# Low_MOS.net
KiCad netlist of a schematic drawn in Altium Designer
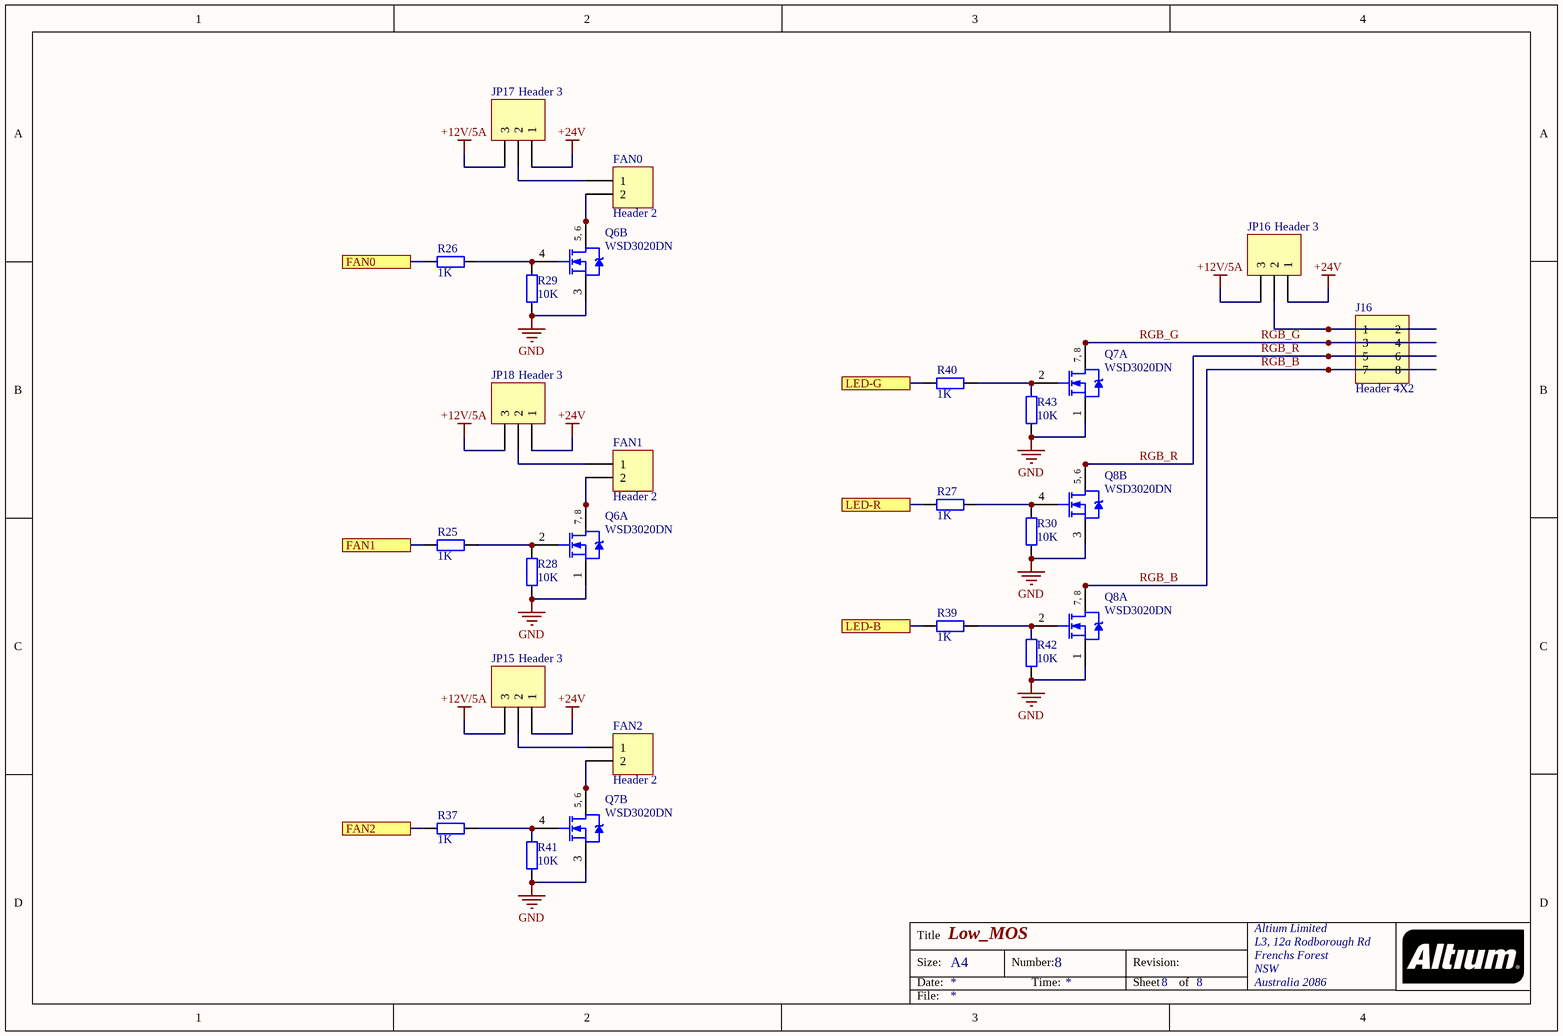
[diagram p0: Low_MOS.SchDoc]

(export (version "E")
  (design (tool "Eeschema 10.0.6"))
  (components
    (comp (ref "FAN0")
      (value "Header 2")
      (footprint "1X2 MTE STRAIGHT HEADER 2.54MM")
      (description "Header, 2-Pin")
      (fields (field (name "PUBLISHER") "Altium Limited"))
      (libsource (lib "Miscellaneous Connectors") (part "Header 2"))
    )
    (comp (ref "FAN1")
      (value "Header 2")
      (footprint "1X2 MTE STRAIGHT HEADER 2.54MM")
      (description "Header, 2-Pin")
      (fields (field (name "PUBLISHER") "Altium Limited"))
      (libsource (lib "Miscellaneous Connectors") (part "Header 2"))
    )
    (comp (ref "FAN2")
      (value "Header 2")
      (footprint "1X2 MTE STRAIGHT HEADER 2.54MM")
      (description "Header, 2-Pin")
      (fields (field (name "PUBLISHER") "Altium Limited"))
      (libsource (lib "Miscellaneous Connectors") (part "Header 2"))
    )
    (comp (ref "J16")
      (value "Header 4X2")
      (footprint "Header 2X4")
      (description "Header, 4-Pin, Dual row")
      (fields (field (name "PUBLISHER") "Altium Limited"))
      (libsource (lib "Miscellaneous Connectors") (part "Header 4X2"))
    )
    (comp (ref "JP15")
      (value "Header 3")
      (footprint "Header 1X3")
      (description "Header, 3-Pin")
      (fields (field (name "PUBLISHER") "Altium Limited"))
      (libsource (lib "Miscellaneous Connectors") (part "Header 3"))
    )
    (comp (ref "JP16")
      (value "Header 3")
      (footprint "Header 1X3")
      (description "Header, 3-Pin")
      (fields (field (name "PUBLISHER") "Altium Limited"))
      (libsource (lib "Miscellaneous Connectors") (part "Header 3"))
    )
    (comp (ref "JP17")
      (value "Header 3")
      (footprint "Header 1X3")
      (description "Header, 3-Pin")
      (fields (field (name "PUBLISHER") "Altium Limited"))
      (libsource (lib "Miscellaneous Connectors") (part "Header 3"))
    )
    (comp (ref "JP18")
      (value "Header 3")
      (footprint "Header 1X3")
      (description "Header, 3-Pin")
      (fields (field (name "PUBLISHER") "Altium Limited"))
      (libsource (lib "Miscellaneous Connectors") (part "Header 3"))
    )
    (comp (ref "Q6")
      (value "WSD3020DN")
      (footprint "DFN3X3-8L-Dual")
      (description "HEXFET Power MOSFET")
      (fields (field (name "PUBLISHER") "Altium Limited"))
      (libsource (lib "IR Discrete MOSFET - Power") (part "IRF7103"))
    )
    (comp (ref "Q7")
      (value "WSD3020DN")
      (footprint "DFN3X3-8L-Dual")
      (description "HEXFET Power MOSFET")
      (fields (field (name "PUBLISHER") "Altium Limited"))
      (libsource (lib "IR Discrete MOSFET - Power") (part "IRF7103"))
    )
    (comp (ref "Q8")
      (value "WSD3020DN")
      (footprint "DFN3X3-8L-Dual")
      (description "HEXFET Power MOSFET")
      (fields (field (name "PUBLISHER") "Altium Limited"))
      (libsource (lib "IR Discrete MOSFET - Power") (part "IRF7103"))
    )
    (comp (ref "R25") (value "1K") (footprint "RES0402") (libsource (lib "接插件库") (part "Resistor")))
    (comp (ref "R26") (value "1K") (footprint "RES0402") (libsource (lib "接插件库") (part "Resistor")))
    (comp (ref "R27") (value "1K") (footprint "RES0402") (libsource (lib "接插件库") (part "Resistor")))
    (comp (ref "R28") (value "10K") (footprint "RES0402") (libsource (lib "") (part "Resistor_1")))
    (comp (ref "R29") (value "10K") (footprint "RES0402") (libsource (lib "") (part "Resistor_1")))
    (comp (ref "R30") (value "10K") (footprint "RES0402") (libsource (lib "") (part "Resistor_1")))
    (comp (ref "R37") (value "1K") (footprint "RES0402") (libsource (lib "接插件库") (part "Resistor")))
    (comp (ref "R39") (value "1K") (footprint "RES0402") (libsource (lib "接插件库") (part "Resistor")))
    (comp (ref "R40") (value "1K") (footprint "RES0402") (libsource (lib "接插件库") (part "Resistor")))
    (comp (ref "R41") (value "10K") (footprint "RES0402") (libsource (lib "") (part "Resistor_1")))
    (comp (ref "R42") (value "10K") (footprint "RES0402") (libsource (lib "") (part "Resistor_1")))
    (comp (ref "R43") (value "10K") (footprint "RES0402") (libsource (lib "") (part "Resistor_1")))
  )
  (nets
    (net (code "1") (name "+12V{slash}5A") (class "Default")
      (node (ref "JP15") (pin "3") (pinfunction "3_3") (pintype "passive"))
      (node (ref "JP16") (pin "3") (pinfunction "3_3") (pintype "passive"))
      (node (ref "JP17") (pin "3") (pinfunction "3_3") (pintype "passive"))
      (node (ref "JP18") (pin "3") (pinfunction "3_3") (pintype "passive"))
    )
    (net (code "2") (name "+24V") (class "Default")
      (node (ref "JP15") (pin "1") (pinfunction "1_1") (pintype "passive"))
      (node (ref "JP16") (pin "1") (pinfunction "1_1") (pintype "passive"))
      (node (ref "JP17") (pin "1") (pinfunction "1_1") (pintype "passive"))
      (node (ref "JP18") (pin "1") (pinfunction "1_1") (pintype "passive"))
    )
    (net (code "3") (name "/FAN0") (class "Default")
      (node (ref "R26") (pin "1") (pinfunction "1_1") (pintype "passive"))
    )
    (net (code "4") (name "/FAN1") (class "Default")
      (node (ref "R25") (pin "1") (pinfunction "1_1") (pintype "passive"))
    )
    (net (code "5") (name "/FAN2") (class "Default")
      (node (ref "R37") (pin "1") (pinfunction "1_1") (pintype "passive"))
    )
    (net (code "6") (name "/LED-B") (class "Default")
      (node (ref "R39") (pin "1") (pinfunction "1_1") (pintype "passive"))
    )
    (net (code "7") (name "/LED-G") (class "Default")
      (node (ref "R40") (pin "1") (pinfunction "1_1") (pintype "passive"))
    )
    (net (code "8") (name "/LED-R") (class "Default")
      (node (ref "R27") (pin "1") (pinfunction "1_1") (pintype "passive"))
    )
    (net (code "9") (name "/RGB_B") (class "Default")
      (node (ref "J16") (pin "7") (pinfunction "7_7") (pintype "passive"))
      (node (ref "J16") (pin "8") (pinfunction "8_8") (pintype "passive"))
      (node (ref "Q8") (pin "7") (pinfunction "D_7") (pintype "passive"))
      (node (ref "Q8") (pin "8") (pinfunction "D_8") (pintype "passive"))
    )
    (net (code "10") (name "/RGB_G") (class "Default")
      (node (ref "J16") (pin "3") (pinfunction "3_3") (pintype "passive"))
      (node (ref "J16") (pin "4") (pinfunction "4_4") (pintype "passive"))
      (node (ref "Q7") (pin "7") (pinfunction "D_7") (pintype "passive"))
      (node (ref "Q7") (pin "8") (pinfunction "D_8") (pintype "passive"))
    )
    (net (code "11") (name "/RGB_R") (class "Default")
      (node (ref "J16") (pin "5") (pinfunction "5_5") (pintype "passive"))
      (node (ref "J16") (pin "6") (pinfunction "6_6") (pintype "passive"))
      (node (ref "Q8") (pin "5") (pinfunction "D_5") (pintype "passive"))
      (node (ref "Q8") (pin "6") (pinfunction "D_6") (pintype "passive"))
    )
    (net (code "12") (name "GND") (class "Default")
      (node (ref "Q6") (pin "1") (pinfunction "S_1") (pintype "passive"))
      (node (ref "Q6") (pin "3") (pinfunction "S_3") (pintype "passive"))
      (node (ref "Q7") (pin "1") (pinfunction "S_1") (pintype "passive"))
      (node (ref "Q7") (pin "3") (pinfunction "S_3") (pintype "passive"))
      (node (ref "Q8") (pin "1") (pinfunction "S_1") (pintype "passive"))
      (node (ref "Q8") (pin "3") (pinfunction "S_3") (pintype "passive"))
      (node (ref "R28") (pin "2") (pinfunction "2_2") (pintype "passive"))
      (node (ref "R29") (pin "2") (pinfunction "2_2") (pintype "passive"))
      (node (ref "R30") (pin "2") (pinfunction "2_2") (pintype "passive"))
      (node (ref "R41") (pin "2") (pinfunction "2_2") (pintype "passive"))
      (node (ref "R42") (pin "2") (pinfunction "2_2") (pintype "passive"))
      (node (ref "R43") (pin "2") (pinfunction "2_2") (pintype "passive"))
    )
    (net (code "13") (name "Net-(FAN0-Pad1)") (class "Default")
      (node (ref "FAN0") (pin "1") (pinfunction "1_1") (pintype "passive"))
      (node (ref "JP17") (pin "2") (pinfunction "2_2") (pintype "passive"))
    )
    (net (code "14") (name "Net-(FAN0-Pad2)") (class "Default")
      (node (ref "FAN0") (pin "2") (pinfunction "2_2") (pintype "passive"))
      (node (ref "Q6") (pin "5") (pinfunction "D_5") (pintype "passive"))
      (node (ref "Q6") (pin "6") (pinfunction "D_6") (pintype "passive"))
    )
    (net (code "15") (name "Net-(FAN1-Pad1)") (class "Default")
      (node (ref "FAN1") (pin "1") (pinfunction "1_1") (pintype "passive"))
      (node (ref "JP18") (pin "2") (pinfunction "2_2") (pintype "passive"))
    )
    (net (code "16") (name "Net-(FAN1-Pad2)") (class "Default")
      (node (ref "FAN1") (pin "2") (pinfunction "2_2") (pintype "passive"))
      (node (ref "Q6") (pin "7") (pinfunction "D_7") (pintype "passive"))
      (node (ref "Q6") (pin "8") (pinfunction "D_8") (pintype "passive"))
    )
    (net (code "17") (name "Net-(FAN2-Pad1)") (class "Default")
      (node (ref "FAN2") (pin "1") (pinfunction "1_1") (pintype "passive"))
      (node (ref "JP15") (pin "2") (pinfunction "2_2") (pintype "passive"))
    )
    (net (code "18") (name "Net-(FAN2-Pad2)") (class "Default")
      (node (ref "FAN2") (pin "2") (pinfunction "2_2") (pintype "passive"))
      (node (ref "Q7") (pin "5") (pinfunction "D_5") (pintype "passive"))
      (node (ref "Q7") (pin "6") (pinfunction "D_6") (pintype "passive"))
    )
    (net (code "19") (name "Net-(J16-Pad1)") (class "Default")
      (node (ref "J16") (pin "1") (pinfunction "1_1") (pintype "passive"))
      (node (ref "J16") (pin "2") (pinfunction "2_2") (pintype "passive"))
      (node (ref "JP16") (pin "2") (pinfunction "2_2") (pintype "passive"))
    )
    (net (code "20") (name "Net-(Q6A-G)") (class "Default")
      (node (ref "Q6") (pin "2") (pinfunction "G_2") (pintype "passive"))
      (node (ref "R25") (pin "2") (pinfunction "2_2") (pintype "passive"))
      (node (ref "R28") (pin "1") (pinfunction "1_1") (pintype "passive"))
    )
    (net (code "21") (name "Net-(Q6B-G)") (class "Default")
      (node (ref "Q6") (pin "4") (pinfunction "G_4") (pintype "passive"))
      (node (ref "R26") (pin "2") (pinfunction "2_2") (pintype "passive"))
      (node (ref "R29") (pin "1") (pinfunction "1_1") (pintype "passive"))
    )
    (net (code "22") (name "Net-(Q7A-G)") (class "Default")
      (node (ref "Q7") (pin "2") (pinfunction "G_2") (pintype "passive"))
      (node (ref "R40") (pin "2") (pinfunction "2_2") (pintype "passive"))
      (node (ref "R43") (pin "1") (pinfunction "1_1") (pintype "passive"))
    )
    (net (code "23") (name "Net-(Q7B-G)") (class "Default")
      (node (ref "Q7") (pin "4") (pinfunction "G_4") (pintype "passive"))
      (node (ref "R37") (pin "2") (pinfunction "2_2") (pintype "passive"))
      (node (ref "R41") (pin "1") (pinfunction "1_1") (pintype "passive"))
    )
    (net (code "24") (name "Net-(Q8A-G)") (class "Default")
      (node (ref "Q8") (pin "2") (pinfunction "G_2") (pintype "passive"))
      (node (ref "R39") (pin "2") (pinfunction "2_2") (pintype "passive"))
      (node (ref "R42") (pin "1") (pinfunction "1_1") (pintype "passive"))
    )
    (net (code "25") (name "Net-(Q8B-G)") (class "Default")
      (node (ref "Q8") (pin "4") (pinfunction "G_4") (pintype "passive"))
      (node (ref "R27") (pin "2") (pinfunction "2_2") (pintype "passive"))
      (node (ref "R30") (pin "1") (pinfunction "1_1") (pintype "passive"))
    )
  )
)
